# K7410tFFG900Aux.net
KiCad netlist of a schematic drawn in Altium Designer
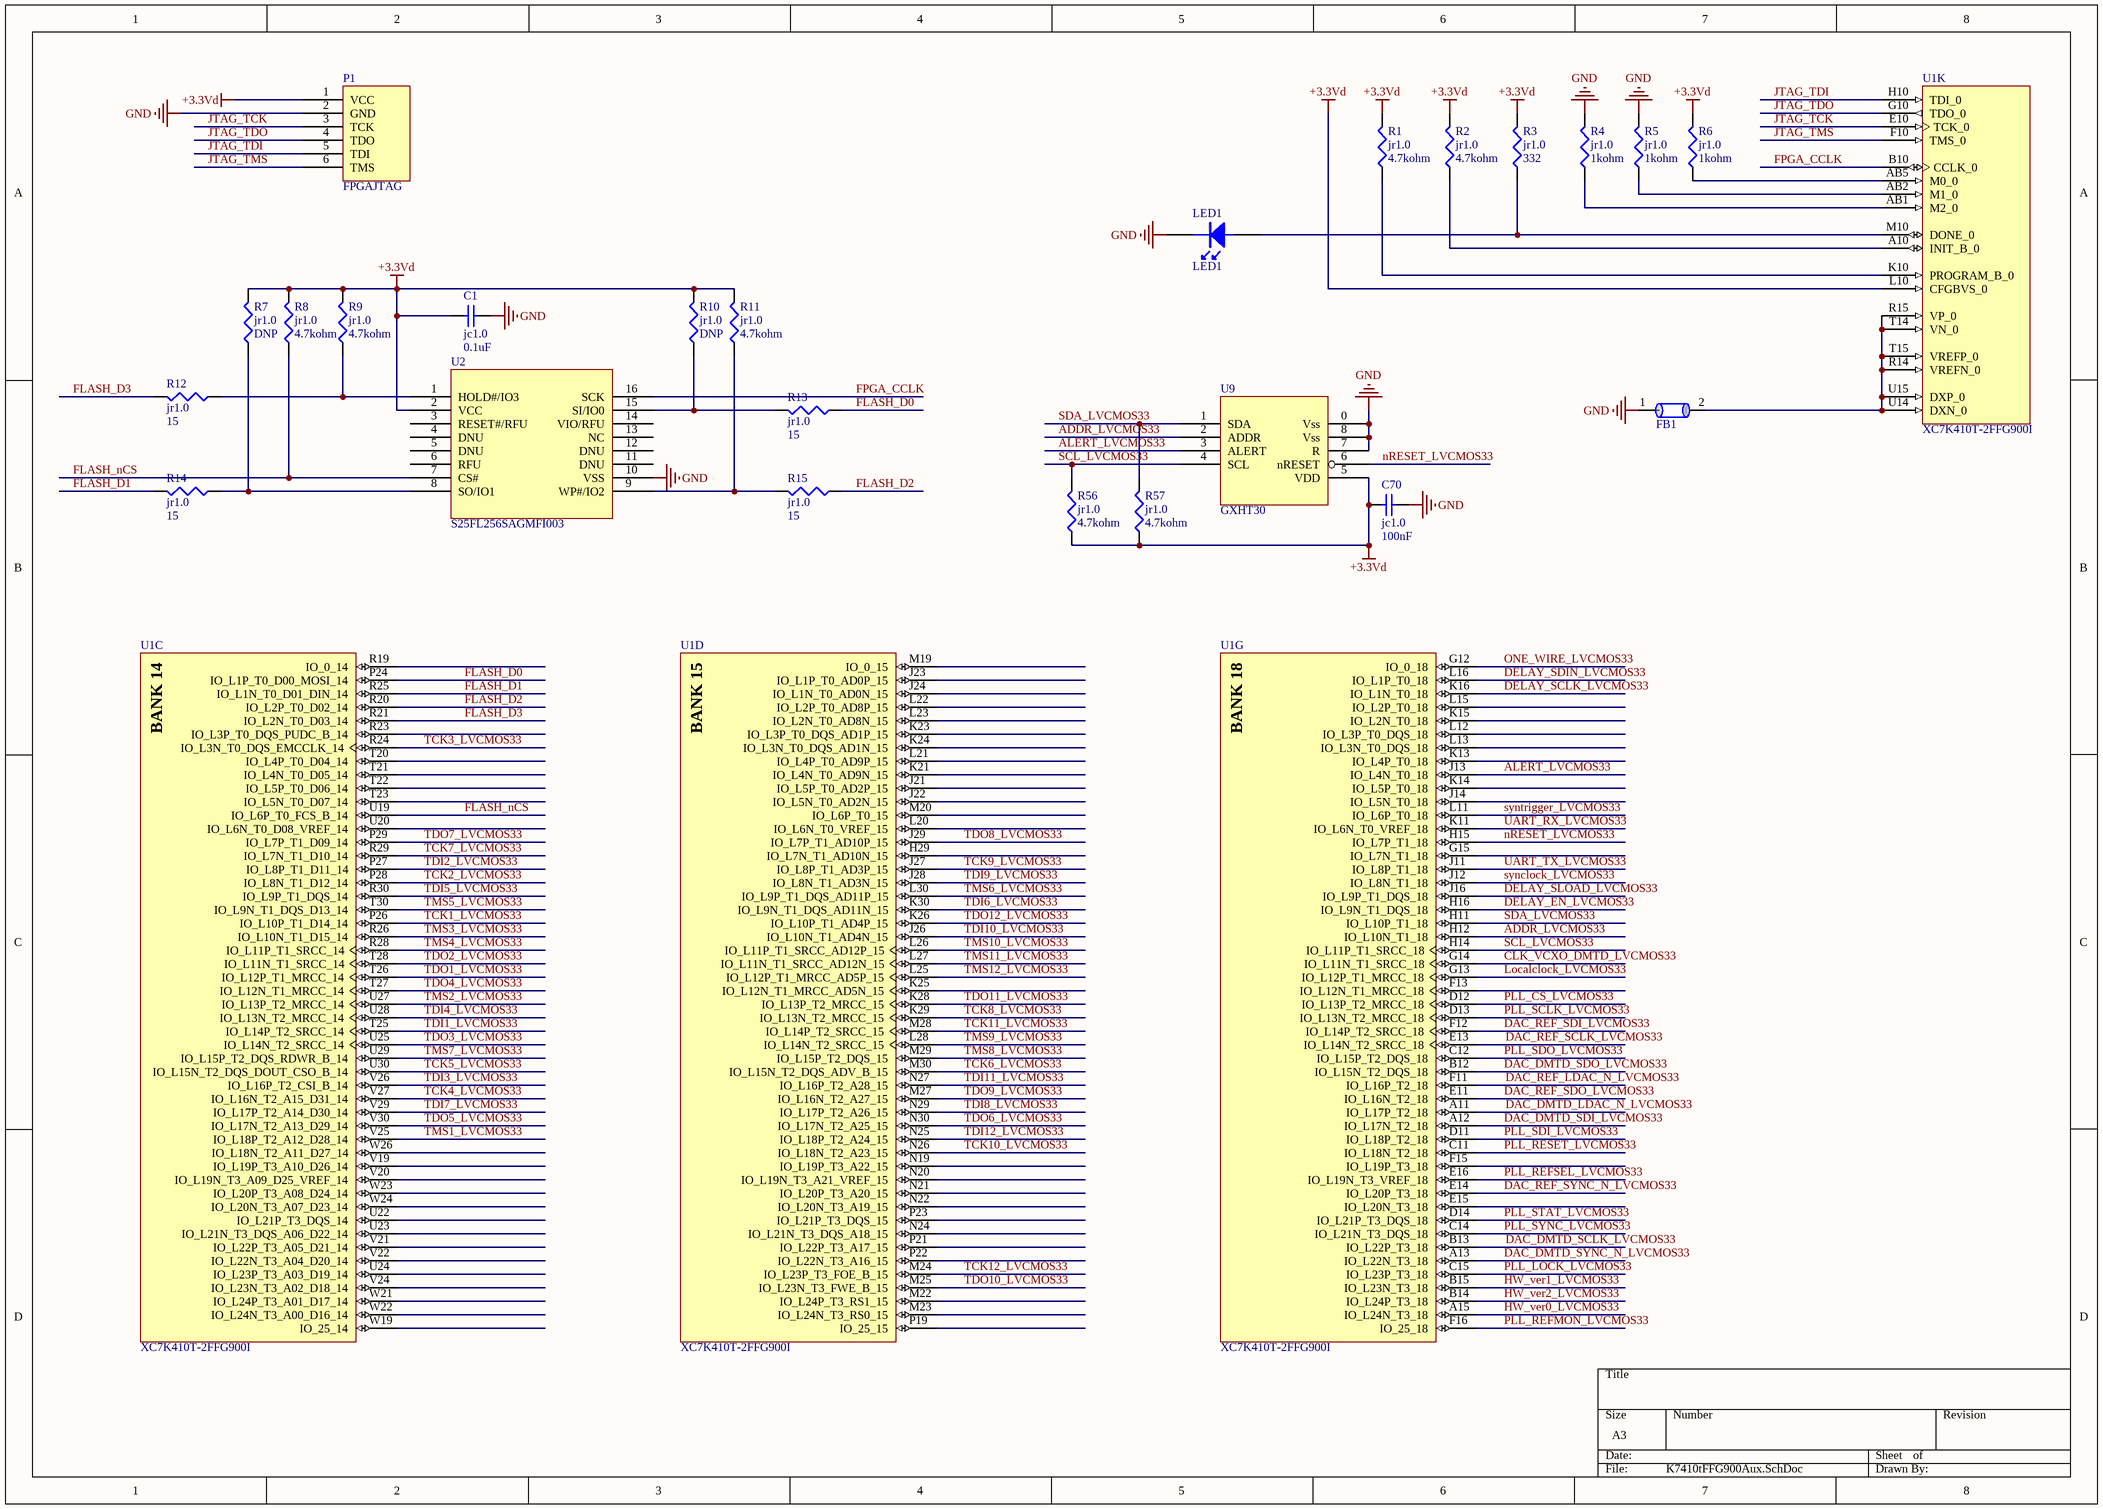
[diagram p0: K7410tFFG900Aux.SchDoc]

(export (version "E")
  (design (tool "Eeschema 10.0.6"))
  (components
    (comp (ref "C1")
      (value "jc1.0")
      (footprint "0402")
      (description "Capacitor")
      (fields (field (name "ALTIUM_VALUE") "0.1uF") (field (name "PUBLISHER") "Altium Limited"))
      (libsource (lib "LIB01DXP2006SchLib") (part "Cap"))
    )
    (comp (ref "C70")
      (value "jc1.0")
      (footprint "0402")
      (description "Capacitor")
      (fields (field (name "ALTIUM_VALUE") "100nF") (field (name "PUBLISHER") "Altium Limited"))
      (libsource (lib "LIB01DXP2006SchLib") (part "Cap"))
    )
    (comp (ref "FB1")
      (value "Ferrite Bead")
      (footprint "0603")
      (libsource (lib "LIB01DXP2006SchLib") (part "FerriteBead"))
    )
    (comp (ref "LED1") (value "LED1") (footprint "LED1") (libsource (lib "LIB01DXP2006SchLib") (part "LED1")))
    (comp (ref "P1")
      (value "FPGAJTAG")
      (footprint "SIP6")
      (libsource (lib "LIB01DXP2006SchLib") (part "FPGAJTAGHEADER"))
    )
    (comp (ref "R1")
      (value "jr1.0")
      (footprint "0402")
      (description "Resistor")
      (fields (field (name "ALTIUM_VALUE") "4.7kohm") (field (name "PUBLISHER") "Altium Limited"))
      (libsource (lib "LIB01DXP2006SchLib") (part "Res"))
    )
    (comp (ref "R2")
      (value "jr1.0")
      (footprint "0402")
      (description "Resistor")
      (fields (field (name "ALTIUM_VALUE") "4.7kohm") (field (name "PUBLISHER") "Altium Limited"))
      (libsource (lib "LIB01DXP2006SchLib") (part "Res"))
    )
    (comp (ref "R3")
      (value "jr1.0")
      (footprint "0402")
      (description "Resistor")
      (fields (field (name "ALTIUM_VALUE") "332") (field (name "PUBLISHER") "Altium Limited"))
      (libsource (lib "LIB01DXP2006SchLib") (part "Res"))
    )
    (comp (ref "R4")
      (value "jr1.0")
      (footprint "0402")
      (description "Resistor")
      (fields (field (name "ALTIUM_VALUE") "1kohm") (field (name "PUBLISHER") "Altium Limited"))
      (libsource (lib "LIB01DXP2006SchLib") (part "Res"))
    )
    (comp (ref "R5")
      (value "jr1.0")
      (footprint "0402")
      (description "Resistor")
      (fields (field (name "ALTIUM_VALUE") "1kohm") (field (name "PUBLISHER") "Altium Limited"))
      (libsource (lib "LIB01DXP2006SchLib") (part "Res"))
    )
    (comp (ref "R6")
      (value "jr1.0")
      (footprint "0402")
      (description "Resistor")
      (fields (field (name "ALTIUM_VALUE") "1kohm") (field (name "PUBLISHER") "Altium Limited"))
      (libsource (lib "LIB01DXP2006SchLib") (part "Res"))
    )
    (comp (ref "R7")
      (value "jr1.0")
      (footprint "0402")
      (description "Resistor")
      (fields (field (name "ALTIUM_VALUE") "DNP") (field (name "PUBLISHER") "Altium Limited"))
      (libsource (lib "LIB01DXP2006SchLib") (part "Res"))
    )
    (comp (ref "R8")
      (value "jr1.0")
      (footprint "0402")
      (description "Resistor")
      (fields (field (name "ALTIUM_VALUE") "4.7kohm") (field (name "PUBLISHER") "Altium Limited"))
      (libsource (lib "LIB01DXP2006SchLib") (part "Res"))
    )
    (comp (ref "R9")
      (value "jr1.0")
      (footprint "0402")
      (description "Resistor")
      (fields (field (name "ALTIUM_VALUE") "4.7kohm") (field (name "PUBLISHER") "Altium Limited"))
      (libsource (lib "LIB01DXP2006SchLib") (part "Res"))
    )
    (comp (ref "R10")
      (value "jr1.0")
      (footprint "0402")
      (description "Resistor")
      (fields (field (name "ALTIUM_VALUE") "DNP") (field (name "PUBLISHER") "Altium Limited"))
      (libsource (lib "LIB01DXP2006SchLib") (part "Res"))
    )
    (comp (ref "R11")
      (value "jr1.0")
      (footprint "0402")
      (description "Resistor")
      (fields (field (name "ALTIUM_VALUE") "4.7kohm") (field (name "PUBLISHER") "Altium Limited"))
      (libsource (lib "LIB01DXP2006SchLib") (part "Res"))
    )
    (comp (ref "R12")
      (value "jr1.0")
      (footprint "0402")
      (description "Resistor")
      (fields (field (name "ALTIUM_VALUE") "15") (field (name "PUBLISHER") "Altium Limited"))
      (libsource (lib "LIB01DXP2006SchLib") (part "Res"))
    )
    (comp (ref "R13")
      (value "jr1.0")
      (footprint "0402")
      (description "Resistor")
      (fields (field (name "ALTIUM_VALUE") "15") (field (name "PUBLISHER") "Altium Limited"))
      (libsource (lib "LIB01DXP2006SchLib") (part "Res"))
    )
    (comp (ref "R14")
      (value "jr1.0")
      (footprint "0402")
      (description "Resistor")
      (fields (field (name "ALTIUM_VALUE") "15") (field (name "PUBLISHER") "Altium Limited"))
      (libsource (lib "LIB01DXP2006SchLib") (part "Res"))
    )
    (comp (ref "R15")
      (value "jr1.0")
      (footprint "0402")
      (description "Resistor")
      (fields (field (name "ALTIUM_VALUE") "15") (field (name "PUBLISHER") "Altium Limited"))
      (libsource (lib "LIB01DXP2006SchLib") (part "Res"))
    )
    (comp (ref "R56")
      (value "jr1.0")
      (footprint "0402")
      (description "Resistor")
      (fields (field (name "ALTIUM_VALUE") "4.7kohm") (field (name "PUBLISHER") "Altium Limited"))
      (libsource (lib "LIB01DXP2006SchLib") (part "Res"))
    )
    (comp (ref "R57")
      (value "jr1.0")
      (footprint "0402")
      (description "Resistor")
      (fields (field (name "ALTIUM_VALUE") "4.7kohm") (field (name "PUBLISHER") "Altium Limited"))
      (libsource (lib "LIB01DXP2006SchLib") (part "Res"))
    )
    (comp (ref "U1")
      (value "XC7K410T-2FFG900I")
      (footprint "FFG900")
      (description "Kintex-7 FPGA, 500 User I/Os, 16 GTX, 900-Ball BGA, Speed Grade 2, Industrial Grade, Pb-Free")
      (fields (field (name "GENERIC PART NUMBER") "XC7K410T") (field (name "MANUFACTURER") "Xilinx"))
      (libsource (lib "Xilinx Kintex-7") (part "XC7K410T-2FFG900I"))
    )
    (comp (ref "U2")
      (value "S25FL256SAGMFI003")
      (footprint "SO3016")
      (libsource (lib "LIB01DXP2006SchLib") (part "S25FL256SAGMFI003"))
    )
    (comp (ref "U9")
      (value "GXHT30")
      (footprint "GXHT30")
      (libsource (lib "LIB01DXP2006SchLib") (part "GXHT30"))
    )
  )
  (nets
    (net (code "1") (name "+3.3Vd") (class "Default")
      (node (ref "C1") (pin "2") (pinfunction "2_2") (pintype "passive"))
      (node (ref "C70") (pin "1") (pinfunction "1_1") (pintype "passive"))
      (node (ref "P1") (pin "1") (pinfunction "VCC_1") (pintype "passive"))
      (node (ref "R1") (pin "2") (pinfunction "2_2") (pintype "passive"))
      (node (ref "R10") (pin "2") (pinfunction "2_2") (pintype "passive"))
      (node (ref "R11") (pin "2") (pinfunction "2_2") (pintype "passive"))
      (node (ref "R2") (pin "2") (pinfunction "2_2") (pintype "passive"))
      (node (ref "R3") (pin "2") (pinfunction "2_2") (pintype "passive"))
      (node (ref "R56") (pin "1") (pinfunction "1_1") (pintype "passive"))
      (node (ref "R57") (pin "1") (pinfunction "1_1") (pintype "passive"))
      (node (ref "R6") (pin "2") (pinfunction "2_2") (pintype "passive"))
      (node (ref "R7") (pin "2") (pinfunction "2_2") (pintype "passive"))
      (node (ref "R8") (pin "2") (pinfunction "2_2") (pintype "passive"))
      (node (ref "R9") (pin "2") (pinfunction "2_2") (pintype "passive"))
      (node (ref "U1") (pin "L10") (pinfunction "CFGBVS_0_L10") (pintype "input"))
      (node (ref "U2") (pin "2") (pinfunction "VCC_2") (pintype "passive"))
      (node (ref "U9") (pin "5") (pinfunction "VDD_5") (pintype "passive"))
    )
    (net (code "2") (name "/ADDR_LVCMOS33") (class "Default")
      (node (ref "U1") (pin "H12") (pinfunction "IO_L10N_T1_18_H12") (pintype "bidirectional"))
      (node (ref "U9") (pin "2") (pinfunction "ADDR_2") (pintype "passive"))
    )
    (net (code "3") (name "/ALERT_LVCMOS33") (class "Default")
      (node (ref "U1") (pin "J13") (pinfunction "IO_L4N_T0_18_J13") (pintype "bidirectional"))
      (node (ref "U9") (pin "3") (pinfunction "ALERT_3") (pintype "passive"))
    )
    (net (code "4") (name "/CLK_VCXO_DMTD_LVCMOS33") (class "Default")
      (node (ref "U1") (pin "G14") (pinfunction "IO_L11N_T1_SRCC_18_G14") (pintype "bidirectional"))
    )
    (net (code "5") (name "/DAC_DMTD_LDAC_N_LVCMOS33") (class "Default")
      (node (ref "U1") (pin "A11") (pinfunction "IO_L17P_T2_18_A11") (pintype "bidirectional"))
    )
    (net (code "6") (name "/DAC_DMTD_SCLK_LVCMOS33") (class "Default")
      (node (ref "U1") (pin "B13") (pinfunction "IO_L22P_T3_18_B13") (pintype "bidirectional"))
    )
    (net (code "7") (name "/DAC_DMTD_SDI_LVCMOS33") (class "Default")
      (node (ref "U1") (pin "A12") (pinfunction "IO_L17N_T2_18_A12") (pintype "bidirectional"))
    )
    (net (code "8") (name "/DAC_DMTD_SDO_LVCMOS33") (class "Default")
      (node (ref "U1") (pin "B12") (pinfunction "IO_L15N_T2_DQS_18_B12") (pintype "bidirectional"))
    )
    (net (code "9") (name "/DAC_DMTD_SYNC_N_LVCMOS33") (class "Default")
      (node (ref "U1") (pin "A13") (pinfunction "IO_L22N_T3_18_A13") (pintype "bidirectional"))
    )
    (net (code "10") (name "/DAC_REF_LDAC_N_LVCMOS33") (class "Default")
      (node (ref "U1") (pin "F11") (pinfunction "IO_L16P_T2_18_F11") (pintype "bidirectional"))
    )
    (net (code "11") (name "/DAC_REF_SCLK_LVCMOS33") (class "Default")
      (node (ref "U1") (pin "E13") (pinfunction "IO_L14N_T2_SRCC_18_E13") (pintype "bidirectional"))
    )
    (net (code "12") (name "/DAC_REF_SDI_LVCMOS33") (class "Default")
      (node (ref "U1") (pin "F12") (pinfunction "IO_L14P_T2_SRCC_18_F12") (pintype "bidirectional"))
    )
    (net (code "13") (name "/DAC_REF_SDO_LVCMOS33") (class "Default")
      (node (ref "U1") (pin "E11") (pinfunction "IO_L16N_T2_18_E11") (pintype "bidirectional"))
    )
    (net (code "14") (name "/DAC_REF_SYNC_N_LVCMOS33") (class "Default")
      (node (ref "U1") (pin "E14") (pinfunction "IO_L20P_T3_18_E14") (pintype "bidirectional"))
    )
    (net (code "15") (name "/DELAY_EN_LVCMOS33") (class "Default")
      (node (ref "U1") (pin "H16") (pinfunction "IO_L9N_T1_DQS_18_H16") (pintype "bidirectional"))
    )
    (net (code "16") (name "/DELAY_SCLK_LVCMOS33") (class "Default")
      (node (ref "U1") (pin "K16") (pinfunction "IO_L1N_T0_18_K16") (pintype "bidirectional"))
    )
    (net (code "17") (name "/DELAY_SDIN_LVCMOS33") (class "Default")
      (node (ref "U1") (pin "L16") (pinfunction "IO_L1P_T0_18_L16") (pintype "bidirectional"))
    )
    (net (code "18") (name "/DELAY_SLOAD_LVCMOS33") (class "Default")
      (node (ref "U1") (pin "J16") (pinfunction "IO_L9P_T1_DQS_18_J16") (pintype "bidirectional"))
    )
    (net (code "19") (name "/FLASH_D0") (class "Default")
      (node (ref "R13") (pin "1") (pinfunction "1_1") (pintype "passive"))
      (node (ref "U1") (pin "P24") (pinfunction "IO_L1P_T0_D00_MOSI_14_P24") (pintype "bidirectional"))
    )
    (net (code "20") (name "/FLASH_D1") (class "Default")
      (node (ref "R14") (pin "2") (pinfunction "2_2") (pintype "passive"))
      (node (ref "U1") (pin "R25") (pinfunction "IO_L1N_T0_D01_DIN_14_R25") (pintype "bidirectional"))
    )
    (net (code "21") (name "/FLASH_D2") (class "Default")
      (node (ref "R15") (pin "1") (pinfunction "1_1") (pintype "passive"))
      (node (ref "U1") (pin "R20") (pinfunction "IO_L2P_T0_D02_14_R20") (pintype "bidirectional"))
    )
    (net (code "22") (name "/FLASH_D3") (class "Default")
      (node (ref "R12") (pin "2") (pinfunction "2_2") (pintype "passive"))
      (node (ref "U1") (pin "R21") (pinfunction "IO_L2N_T0_D03_14_R21") (pintype "bidirectional"))
    )
    (net (code "23") (name "/FLASH_nCS") (class "Default")
      (node (ref "R8") (pin "1") (pinfunction "1_1") (pintype "passive"))
      (node (ref "U1") (pin "U19") (pinfunction "IO_L6P_T0_FCS_B_14_U19") (pintype "bidirectional"))
      (node (ref "U2") (pin "7") (pinfunction "CS#_7") (pintype "passive"))
    )
    (net (code "24") (name "/FPGA_CCLK") (class "Default")
      (node (ref "U1") (pin "B10") (pinfunction "CCLK_0_B10") (pintype "bidirectional"))
      (node (ref "U2") (pin "16") (pinfunction "SCK_16") (pintype "passive"))
    )
    (net (code "25") (name "/HW_ver0_LVCMOS33") (class "Default")
      (node (ref "U1") (pin "A15") (pinfunction "IO_L24N_T3_18_A15") (pintype "bidirectional"))
    )
    (net (code "26") (name "/HW_ver1_LVCMOS33") (class "Default")
      (node (ref "U1") (pin "B15") (pinfunction "IO_L23N_T3_18_B15") (pintype "bidirectional"))
    )
    (net (code "27") (name "/HW_ver2_LVCMOS33") (class "Default")
      (node (ref "U1") (pin "B14") (pinfunction "IO_L24P_T3_18_B14") (pintype "bidirectional"))
    )
    (net (code "28") (name "/JTAG_TCK") (class "Default")
      (node (ref "P1") (pin "3") (pinfunction "TCK_3") (pintype "passive"))
      (node (ref "U1") (pin "E10") (pinfunction "TCK_0_E10") (pintype "input"))
    )
    (net (code "29") (name "/JTAG_TDI") (class "Default")
      (node (ref "P1") (pin "5") (pinfunction "TDI_5") (pintype "passive"))
      (node (ref "U1") (pin "H10") (pinfunction "TDI_0_H10") (pintype "input"))
    )
    (net (code "30") (name "/JTAG_TDO") (class "Default")
      (node (ref "P1") (pin "4") (pinfunction "TDO_4") (pintype "passive"))
      (node (ref "U1") (pin "G10") (pinfunction "TDO_0_G10") (pintype "output"))
    )
    (net (code "31") (name "/JTAG_TMS") (class "Default")
      (node (ref "P1") (pin "6") (pinfunction "TMS_6") (pintype "passive"))
      (node (ref "U1") (pin "F10") (pinfunction "TMS_0_F10") (pintype "input"))
    )
    (net (code "32") (name "/Localclock_LVCMOS33") (class "Default")
      (node (ref "U1") (pin "G13") (pinfunction "IO_L12P_T1_MRCC_18_G13") (pintype "bidirectional"))
    )
    (net (code "33") (name "/ONE_WIRE_LVCMOS33") (class "Default")
      (node (ref "U1") (pin "G12") (pinfunction "IO_0_18_G12") (pintype "bidirectional"))
    )
    (net (code "34") (name "/PLL_CS_LVCMOS33") (class "Default")
      (node (ref "U1") (pin "D12") (pinfunction "IO_L13P_T2_MRCC_18_D12") (pintype "bidirectional"))
    )
    (net (code "35") (name "/PLL_LOCK_LVCMOS33") (class "Default")
      (node (ref "U1") (pin "C15") (pinfunction "IO_L23P_T3_18_C15") (pintype "bidirectional"))
    )
    (net (code "36") (name "/PLL_REFMON_LVCMOS33") (class "Default")
      (node (ref "U1") (pin "F16") (pinfunction "IO_25_18_F16") (pintype "bidirectional"))
    )
    (net (code "37") (name "/PLL_REFSEL_LVCMOS33") (class "Default")
      (node (ref "U1") (pin "E16") (pinfunction "IO_L19N_T3_VREF_18_E16") (pintype "bidirectional"))
    )
    (net (code "38") (name "/PLL_RESET_LVCMOS33") (class "Default")
      (node (ref "U1") (pin "C11") (pinfunction "IO_L18N_T2_18_C11") (pintype "bidirectional"))
    )
    (net (code "39") (name "/PLL_SCLK_LVCMOS33") (class "Default")
      (node (ref "U1") (pin "D13") (pinfunction "IO_L13N_T2_MRCC_18_D13") (pintype "bidirectional"))
    )
    (net (code "40") (name "/PLL_SDI_LVCMOS33") (class "Default")
      (node (ref "U1") (pin "D11") (pinfunction "IO_L18P_T2_18_D11") (pintype "bidirectional"))
    )
    (net (code "41") (name "/PLL_SDO_LVCMOS33") (class "Default")
      (node (ref "U1") (pin "C12") (pinfunction "IO_L15P_T2_DQS_18_C12") (pintype "bidirectional"))
    )
    (net (code "42") (name "/PLL_STAT_LVCMOS33") (class "Default")
      (node (ref "U1") (pin "D14") (pinfunction "IO_L21P_T3_DQS_18_D14") (pintype "bidirectional"))
    )
    (net (code "43") (name "/PLL_SYNC_LVCMOS33") (class "Default")
      (node (ref "U1") (pin "C14") (pinfunction "IO_L21N_T3_DQS_18_C14") (pintype "bidirectional"))
    )
    (net (code "44") (name "/SCL_LVCMOS33") (class "Default")
      (node (ref "R56") (pin "2") (pinfunction "2_2") (pintype "passive"))
      (node (ref "U1") (pin "H14") (pinfunction "IO_L11P_T1_SRCC_18_H14") (pintype "bidirectional"))
      (node (ref "U9") (pin "4") (pinfunction "SCL_4") (pintype "passive"))
    )
    (net (code "45") (name "/SDA_LVCMOS33") (class "Default")
      (node (ref "R57") (pin "2") (pinfunction "2_2") (pintype "passive"))
      (node (ref "U1") (pin "H11") (pinfunction "IO_L10P_T1_18_H11") (pintype "bidirectional"))
      (node (ref "U9") (pin "1") (pinfunction "SDA_1") (pintype "passive"))
    )
    (net (code "46") (name "/TCK1_LVCMOS33") (class "Default")
      (node (ref "U1") (pin "P26") (pinfunction "IO_L10P_T1_D14_14_P26") (pintype "bidirectional"))
    )
    (net (code "47") (name "/TCK2_LVCMOS33") (class "Default")
      (node (ref "U1") (pin "P28") (pinfunction "IO_L8N_T1_D12_14_P28") (pintype "bidirectional"))
    )
    (net (code "48") (name "/TCK3_LVCMOS33") (class "Default")
      (node (ref "U1") (pin "R24") (pinfunction "IO_L3N_T0_DQS_EMCCLK_14_R24") (pintype "bidirectional"))
    )
    (net (code "49") (name "/TCK4_LVCMOS33") (class "Default")
      (node (ref "U1") (pin "V27") (pinfunction "IO_L16N_T2_A15_D31_14_V27") (pintype "bidirectional"))
    )
    (net (code "50") (name "/TCK5_LVCMOS33") (class "Default")
      (node (ref "U1") (pin "U30") (pinfunction "IO_L15N_T2_DQS_DOUT_CSO_B_14_U30") (pintype "bidirectional"))
    )
    (net (code "51") (name "/TCK6_LVCMOS33") (class "Default")
      (node (ref "U1") (pin "M30") (pinfunction "IO_L15N_T2_DQS_ADV_B_15_M30") (pintype "bidirectional"))
    )
    (net (code "52") (name "/TCK7_LVCMOS33") (class "Default")
      (node (ref "U1") (pin "R29") (pinfunction "IO_L7N_T1_D10_14_R29") (pintype "bidirectional"))
    )
    (net (code "53") (name "/TCK8_LVCMOS33") (class "Default")
      (node (ref "U1") (pin "K29") (pinfunction "IO_L13N_T2_MRCC_15_K29") (pintype "bidirectional"))
    )
    (net (code "54") (name "/TCK9_LVCMOS33") (class "Default")
      (node (ref "U1") (pin "J27") (pinfunction "IO_L8P_T1_AD3P_15_J27") (pintype "bidirectional"))
    )
    (net (code "55") (name "/TCK10_LVCMOS33") (class "Default")
      (node (ref "U1") (pin "N26") (pinfunction "IO_L18N_T2_A23_15_N26") (pintype "bidirectional"))
    )
    (net (code "56") (name "/TCK11_LVCMOS33") (class "Default")
      (node (ref "U1") (pin "M28") (pinfunction "IO_L14P_T2_SRCC_15_M28") (pintype "bidirectional"))
    )
    (net (code "57") (name "/TCK12_LVCMOS33") (class "Default")
      (node (ref "U1") (pin "M24") (pinfunction "IO_L23P_T3_FOE_B_15_M24") (pintype "bidirectional"))
    )
    (net (code "58") (name "/TDI1_LVCMOS33") (class "Default")
      (node (ref "U1") (pin "T25") (pinfunction "IO_L14P_T2_SRCC_14_T25") (pintype "bidirectional"))
    )
    (net (code "59") (name "/TDI2_LVCMOS33") (class "Default")
      (node (ref "U1") (pin "P27") (pinfunction "IO_L8P_T1_D11_14_P27") (pintype "bidirectional"))
    )
    (net (code "60") (name "/TDI3_LVCMOS33") (class "Default")
      (node (ref "U1") (pin "V26") (pinfunction "IO_L16P_T2_CSI_B_14_V26") (pintype "bidirectional"))
    )
    (net (code "61") (name "/TDI4_LVCMOS33") (class "Default")
      (node (ref "U1") (pin "U28") (pinfunction "IO_L13N_T2_MRCC_14_U28") (pintype "bidirectional"))
    )
    (net (code "62") (name "/TDI5_LVCMOS33") (class "Default")
      (node (ref "U1") (pin "R30") (pinfunction "IO_L9P_T1_DQS_14_R30") (pintype "bidirectional"))
    )
    (net (code "63") (name "/TDI6_LVCMOS33") (class "Default")
      (node (ref "U1") (pin "K30") (pinfunction "IO_L9N_T1_DQS_AD11N_15_K30") (pintype "bidirectional"))
    )
    (net (code "64") (name "/TDI7_LVCMOS33") (class "Default")
      (node (ref "U1") (pin "V29") (pinfunction "IO_L17P_T2_A14_D30_14_V29") (pintype "bidirectional"))
    )
    (net (code "65") (name "/TDI8_LVCMOS33") (class "Default")
      (node (ref "U1") (pin "N29") (pinfunction "IO_L17P_T2_A26_15_N29") (pintype "bidirectional"))
    )
    (net (code "66") (name "/TDI9_LVCMOS33") (class "Default")
      (node (ref "U1") (pin "J28") (pinfunction "IO_L8N_T1_AD3N_15_J28") (pintype "bidirectional"))
    )
    (net (code "67") (name "/TDI10_LVCMOS33") (class "Default")
      (node (ref "U1") (pin "J26") (pinfunction "IO_L10N_T1_AD4N_15_J26") (pintype "bidirectional"))
    )
    (net (code "68") (name "/TDI11_LVCMOS33") (class "Default")
      (node (ref "U1") (pin "N27") (pinfunction "IO_L16P_T2_A28_15_N27") (pintype "bidirectional"))
    )
    (net (code "69") (name "/TDI12_LVCMOS33") (class "Default")
      (node (ref "U1") (pin "N25") (pinfunction "IO_L18P_T2_A24_15_N25") (pintype "bidirectional"))
    )
    (net (code "70") (name "/TDO1_LVCMOS33") (class "Default")
      (node (ref "U1") (pin "T26") (pinfunction "IO_L12P_T1_MRCC_14_T26") (pintype "bidirectional"))
    )
    (net (code "71") (name "/TDO2_LVCMOS33") (class "Default")
      (node (ref "U1") (pin "T28") (pinfunction "IO_L11N_T1_SRCC_14_T28") (pintype "bidirectional"))
    )
    (net (code "72") (name "/TDO3_LVCMOS33") (class "Default")
      (node (ref "U1") (pin "U25") (pinfunction "IO_L14N_T2_SRCC_14_U25") (pintype "bidirectional"))
    )
    (net (code "73") (name "/TDO4_LVCMOS33") (class "Default")
      (node (ref "U1") (pin "T27") (pinfunction "IO_L12N_T1_MRCC_14_T27") (pintype "bidirectional"))
    )
    (net (code "74") (name "/TDO5_LVCMOS33") (class "Default")
      (node (ref "U1") (pin "V30") (pinfunction "IO_L17N_T2_A13_D29_14_V30") (pintype "bidirectional"))
    )
    (net (code "75") (name "/TDO6_LVCMOS33") (class "Default")
      (node (ref "U1") (pin "N30") (pinfunction "IO_L17N_T2_A25_15_N30") (pintype "bidirectional"))
    )
    (net (code "76") (name "/TDO7_LVCMOS33") (class "Default")
      (node (ref "U1") (pin "P29") (pinfunction "IO_L7P_T1_D09_14_P29") (pintype "bidirectional"))
    )
    (net (code "77") (name "/TDO8_LVCMOS33") (class "Default")
      (node (ref "U1") (pin "J29") (pinfunction "IO_L7P_T1_AD10P_15_J29") (pintype "bidirectional"))
    )
    (net (code "78") (name "/TDO9_LVCMOS33") (class "Default")
      (node (ref "U1") (pin "M27") (pinfunction "IO_L16N_T2_A27_15_M27") (pintype "bidirectional"))
    )
    (net (code "79") (name "/TDO10_LVCMOS33") (class "Default")
      (node (ref "U1") (pin "M25") (pinfunction "IO_L23N_T3_FWE_B_15_M25") (pintype "bidirectional"))
    )
    (net (code "80") (name "/TDO11_LVCMOS33") (class "Default")
      (node (ref "U1") (pin "K28") (pinfunction "IO_L13P_T2_MRCC_15_K28") (pintype "bidirectional"))
    )
    (net (code "81") (name "/TDO12_LVCMOS33") (class "Default")
      (node (ref "U1") (pin "K26") (pinfunction "IO_L10P_T1_AD4P_15_K26") (pintype "bidirectional"))
    )
    (net (code "82") (name "/TMS1_LVCMOS33") (class "Default")
      (node (ref "U1") (pin "V25") (pinfunction "IO_L18P_T2_A12_D28_14_V25") (pintype "bidirectional"))
    )
    (net (code "83") (name "/TMS2_LVCMOS33") (class "Default")
      (node (ref "U1") (pin "U27") (pinfunction "IO_L13P_T2_MRCC_14_U27") (pintype "bidirectional"))
    )
    (net (code "84") (name "/TMS3_LVCMOS33") (class "Default")
      (node (ref "U1") (pin "R26") (pinfunction "IO_L10N_T1_D15_14_R26") (pintype "bidirectional"))
    )
    (net (code "85") (name "/TMS4_LVCMOS33") (class "Default")
      (node (ref "U1") (pin "R28") (pinfunction "IO_L11P_T1_SRCC_14_R28") (pintype "bidirectional"))
    )
    (net (code "86") (name "/TMS5_LVCMOS33") (class "Default")
      (node (ref "U1") (pin "T30") (pinfunction "IO_L9N_T1_DQS_D13_14_T30") (pintype "bidirectional"))
    )
    (net (code "87") (name "/TMS6_LVCMOS33") (class "Default")
      (node (ref "U1") (pin "L30") (pinfunction "IO_L9P_T1_DQS_AD11P_15_L30") (pintype "bidirectional"))
    )
    (net (code "88") (name "/TMS7_LVCMOS33") (class "Default")
      (node (ref "U1") (pin "U29") (pinfunction "IO_L15P_T2_DQS_RDWR_B_14_U29") (pintype "bidirectional"))
    )
    (net (code "89") (name "/TMS8_LVCMOS33") (class "Default")
      (node (ref "U1") (pin "M29") (pinfunction "IO_L15P_T2_DQS_15_M29") (pintype "bidirectional"))
    )
    (net (code "90") (name "/TMS9_LVCMOS33") (class "Default")
      (node (ref "U1") (pin "L28") (pinfunction "IO_L14N_T2_SRCC_15_L28") (pintype "bidirectional"))
    )
    (net (code "91") (name "/TMS10_LVCMOS33") (class "Default")
      (node (ref "U1") (pin "L26") (pinfunction "IO_L11P_T1_SRCC_AD12P_15_L26") (pintype "bidirectional"))
    )
    (net (code "92") (name "/TMS11_LVCMOS33") (class "Default")
      (node (ref "U1") (pin "L27") (pinfunction "IO_L11N_T1_SRCC_AD12N_15_L27") (pintype "bidirectional"))
    )
    (net (code "93") (name "/TMS12_LVCMOS33") (class "Default")
      (node (ref "U1") (pin "L25") (pinfunction "IO_L12P_T1_MRCC_AD5P_15_L25") (pintype "bidirectional"))
    )
    (net (code "94") (name "/UART_RX_LVCMOS33") (class "Default")
      (node (ref "U1") (pin "K11") (pinfunction "IO_L6N_T0_VREF_18_K11") (pintype "bidirectional"))
    )
    (net (code "95") (name "/UART_TX_LVCMOS33") (class "Default")
      (node (ref "U1") (pin "J11") (pinfunction "IO_L8P_T1_18_J11") (pintype "bidirectional"))
    )
    (net (code "96") (name "/nRESET_LVCMOS33") (class "Default")
      (node (ref "U1") (pin "H15") (pinfunction "IO_L7P_T1_18_H15") (pintype "bidirectional"))
      (node (ref "U9") (pin "6") (pinfunction "nRESET_6") (pintype "passive"))
    )
    (net (code "97") (name "/synclock_LVCMOS33") (class "Default")
      (node (ref "U1") (pin "J12") (pinfunction "IO_L8N_T1_18_J12") (pintype "bidirectional"))
    )
    (net (code "98") (name "/syntrigger_LVCMOS33") (class "Default")
      (node (ref "U1") (pin "L11") (pinfunction "IO_L6P_T0_18_L11") (pintype "bidirectional"))
    )
    (net (code "99") (name "GND") (class "Default")
      (node (ref "C1") (pin "1") (pinfunction "1_1") (pintype "passive"))
      (node (ref "C70") (pin "2") (pinfunction "2_2") (pintype "passive"))
      (node (ref "FB1") (pin "1") (pinfunction "X_1") (pintype "passive"))
      (node (ref "LED1") (pin "2") (pinfunction "2_2") (pintype "passive"))
      (node (ref "P1") (pin "2") (pinfunction "GND_2") (pintype "passive"))
      (node (ref "R4") (pin "2") (pinfunction "2_2") (pintype "passive"))
      (node (ref "R5") (pin "2") (pinfunction "2_2") (pintype "passive"))
      (node (ref "U2") (pin "10") (pinfunction "VSS_10") (pintype "passive"))
      (node (ref "U9") (pin "0") (pinfunction "Vss_0") (pintype "passive"))
      (node (ref "U9") (pin "7") (pinfunction "R_7") (pintype "passive"))
      (node (ref "U9") (pin "8") (pinfunction "Vss_8") (pintype "passive"))
    )
    (net (code "100") (name "Net-(FB1-Y)") (class "Default")
      (node (ref "FB1") (pin "2") (pinfunction "Y_2") (pintype "passive"))
      (node (ref "U1") (pin "R14") (pinfunction "VREFN_0_R14") (pintype "input"))
      (node (ref "U1") (pin "R15") (pinfunction "VP_0_R15") (pintype "input"))
      (node (ref "U1") (pin "T14") (pinfunction "VN_0_T14") (pintype "input"))
      (node (ref "U1") (pin "T15") (pinfunction "VREFP_0_T15") (pintype "input"))
      (node (ref "U1") (pin "U14") (pinfunction "DXN_0_U14") (pintype "input"))
      (node (ref "U1") (pin "U15") (pinfunction "DXP_0_U15") (pintype "input"))
    )
    (net (code "101") (name "Net-(U1K-DONE_0)") (class "Default")
      (node (ref "LED1") (pin "1") (pinfunction "1_1") (pintype "passive"))
      (node (ref "R3") (pin "1") (pinfunction "1_1") (pintype "passive"))
      (node (ref "U1") (pin "M10") (pinfunction "DONE_0_M10") (pintype "bidirectional"))
    )
    (net (code "102") (name "Net-(U1K-INIT_B_0)") (class "Default")
      (node (ref "R2") (pin "1") (pinfunction "1_1") (pintype "passive"))
      (node (ref "U1") (pin "A10") (pinfunction "INIT_B_0_A10") (pintype "bidirectional"))
    )
    (net (code "103") (name "Net-(U1K-M0_0)") (class "Default")
      (node (ref "R6") (pin "1") (pinfunction "1_1") (pintype "passive"))
      (node (ref "U1") (pin "AB5") (pinfunction "M0_0_AB5") (pintype "input"))
    )
    (net (code "104") (name "Net-(U1K-M1_0)") (class "Default")
      (node (ref "R5") (pin "1") (pinfunction "1_1") (pintype "passive"))
      (node (ref "U1") (pin "AB2") (pinfunction "M1_0_AB2") (pintype "input"))
    )
    (net (code "105") (name "Net-(U1K-M2_0)") (class "Default")
      (node (ref "R4") (pin "1") (pinfunction "1_1") (pintype "passive"))
      (node (ref "U1") (pin "AB1") (pinfunction "M2_0_AB1") (pintype "input"))
    )
    (net (code "106") (name "Net-(U1K-PROGRAM_B_0)") (class "Default")
      (node (ref "R1") (pin "1") (pinfunction "1_1") (pintype "passive"))
      (node (ref "U1") (pin "K10") (pinfunction "PROGRAM_B_0_K10") (pintype "input"))
    )
    (net (code "107") (name "Net-(U2-HOLD#{slash}IO3)") (class "Default")
      (node (ref "R12") (pin "1") (pinfunction "1_1") (pintype "passive"))
      (node (ref "R9") (pin "1") (pinfunction "1_1") (pintype "passive"))
      (node (ref "U2") (pin "1") (pinfunction "HOLD#/IO3_1") (pintype "passive"))
    )
    (net (code "108") (name "Net-(U2-SI{slash}IO0)") (class "Default")
      (node (ref "R10") (pin "1") (pinfunction "1_1") (pintype "passive"))
      (node (ref "R13") (pin "2") (pinfunction "2_2") (pintype "passive"))
      (node (ref "U2") (pin "15") (pinfunction "SI/IO0_15") (pintype "passive"))
    )
    (net (code "109") (name "Net-(U2-SO{slash}IO1)") (class "Default")
      (node (ref "R14") (pin "1") (pinfunction "1_1") (pintype "passive"))
      (node (ref "R7") (pin "1") (pinfunction "1_1") (pintype "passive"))
      (node (ref "U2") (pin "8") (pinfunction "SO/IO1_8") (pintype "passive"))
    )
    (net (code "110") (name "Net-(U2-WP#{slash}IO2)") (class "Default")
      (node (ref "R11") (pin "1") (pinfunction "1_1") (pintype "passive"))
      (node (ref "R15") (pin "2") (pinfunction "2_2") (pintype "passive"))
      (node (ref "U2") (pin "9") (pinfunction "WP#/IO2_9") (pintype "passive"))
    )
    (net (code "111") (name "unconnected-(U1C-IO_0_14-PadR19)") (class "Default")
      (node (ref "U1") (pin "R19") (pinfunction "IO_0_14_R19") (pintype "bidirectional"))
    )
    (net (code "112") (name "unconnected-(U1C-IO_25_14-PadW19)") (class "Default")
      (node (ref "U1") (pin "W19") (pinfunction "IO_25_14_W19") (pintype "bidirectional"))
    )
    (net (code "113") (name "unconnected-(U1C-IO_L3P_T0_DQS_PUDC_B_14-PadR23)") (class "Default")
      (node (ref "U1") (pin "R23") (pinfunction "IO_L3P_T0_DQS_PUDC_B_14_R23") (pintype "bidirectional"))
    )
    (net (code "114") (name "unconnected-(U1C-IO_L4N_T0_D05_14-PadT21)") (class "Default")
      (node (ref "U1") (pin "T21") (pinfunction "IO_L4N_T0_D05_14_T21") (pintype "bidirectional"))
    )
    (net (code "115") (name "unconnected-(U1C-IO_L4P_T0_D04_14-PadT20)") (class "Default")
      (node (ref "U1") (pin "T20") (pinfunction "IO_L4P_T0_D04_14_T20") (pintype "bidirectional"))
    )
    (net (code "116") (name "unconnected-(U1C-IO_L5N_T0_D07_14-PadT23)") (class "Default")
      (node (ref "U1") (pin "T23") (pinfunction "IO_L5N_T0_D07_14_T23") (pintype "bidirectional"))
    )
    (net (code "117") (name "unconnected-(U1C-IO_L5P_T0_D06_14-PadT22)") (class "Default")
      (node (ref "U1") (pin "T22") (pinfunction "IO_L5P_T0_D06_14_T22") (pintype "bidirectional"))
    )
    (net (code "118") (name "unconnected-(U1C-IO_L6N_T0_D08_VREF_14-PadU20)") (class "Default")
      (node (ref "U1") (pin "U20") (pinfunction "IO_L6N_T0_D08_VREF_14_U20") (pintype "bidirectional"))
    )
    (net (code "119") (name "unconnected-(U1C-IO_L18N_T2_A11_D27_14-PadW26)") (class "Default")
      (node (ref "U1") (pin "W26") (pinfunction "IO_L18N_T2_A11_D27_14_W26") (pintype "bidirectional"))
    )
    (net (code "120") (name "unconnected-(U1C-IO_L19N_T3_A09_D25_VREF_14-PadV20)") (class "Default")
      (node (ref "U1") (pin "V20") (pinfunction "IO_L19N_T3_A09_D25_VREF_14_V20") (pintype "bidirectional"))
    )
    (net (code "121") (name "unconnected-(U1C-IO_L19P_T3_A10_D26_14-PadV19)") (class "Default")
      (node (ref "U1") (pin "V19") (pinfunction "IO_L19P_T3_A10_D26_14_V19") (pintype "bidirectional"))
    )
    (net (code "122") (name "unconnected-(U1C-IO_L20N_T3_A07_D23_14-PadW24)") (class "Default")
      (node (ref "U1") (pin "W24") (pinfunction "IO_L20N_T3_A07_D23_14_W24") (pintype "bidirectional"))
    )
    (net (code "123") (name "unconnected-(U1C-IO_L20P_T3_A08_D24_14-PadW23)") (class "Default")
      (node (ref "U1") (pin "W23") (pinfunction "IO_L20P_T3_A08_D24_14_W23") (pintype "bidirectional"))
    )
    (net (code "124") (name "unconnected-(U1C-IO_L21N_T3_DQS_A06_D22_14-PadU23)") (class "Default")
      (node (ref "U1") (pin "U23") (pinfunction "IO_L21N_T3_DQS_A06_D22_14_U23") (pintype "bidirectional"))
    )
    (net (code "125") (name "unconnected-(U1C-IO_L21P_T3_DQS_14-PadU22)") (class "Default")
      (node (ref "U1") (pin "U22") (pinfunction "IO_L21P_T3_DQS_14_U22") (pintype "bidirectional"))
    )
    (net (code "126") (name "unconnected-(U1C-IO_L22N_T3_A04_D20_14-PadV22)") (class "Default")
      (node (ref "U1") (pin "V22") (pinfunction "IO_L22N_T3_A04_D20_14_V22") (pintype "bidirectional"))
    )
    (net (code "127") (name "unconnected-(U1C-IO_L22P_T3_A05_D21_14-PadV21)") (class "Default")
      (node (ref "U1") (pin "V21") (pinfunction "IO_L22P_T3_A05_D21_14_V21") (pintype "bidirectional"))
    )
    (net (code "128") (name "unconnected-(U1C-IO_L23N_T3_A02_D18_14-PadV24)") (class "Default")
      (node (ref "U1") (pin "V24") (pinfunction "IO_L23N_T3_A02_D18_14_V24") (pintype "bidirectional"))
    )
    (net (code "129") (name "unconnected-(U1C-IO_L23P_T3_A03_D19_14-PadU24)") (class "Default")
      (node (ref "U1") (pin "U24") (pinfunction "IO_L23P_T3_A03_D19_14_U24") (pintype "bidirectional"))
    )
    (net (code "130") (name "unconnected-(U1C-IO_L24N_T3_A00_D16_14-PadW22)") (class "Default")
      (node (ref "U1") (pin "W22") (pinfunction "IO_L24N_T3_A00_D16_14_W22") (pintype "bidirectional"))
    )
    (net (code "131") (name "unconnected-(U1C-IO_L24P_T3_A01_D17_14-PadW21)") (class "Default")
      (node (ref "U1") (pin "W21") (pinfunction "IO_L24P_T3_A01_D17_14_W21") (pintype "bidirectional"))
    )
    (net (code "132") (name "unconnected-(U1D-IO_0_15-PadM19)") (class "Default")
      (node (ref "U1") (pin "M19") (pinfunction "IO_0_15_M19") (pintype "bidirectional"))
    )
    (net (code "133") (name "unconnected-(U1D-IO_25_15-PadP19)") (class "Default")
      (node (ref "U1") (pin "P19") (pinfunction "IO_25_15_P19") (pintype "bidirectional"))
    )
    (net (code "134") (name "unconnected-(U1D-IO_L1N_T0_AD0N_15-PadJ24)") (class "Default")
      (node (ref "U1") (pin "J24") (pinfunction "IO_L1N_T0_AD0N_15_J24") (pintype "bidirectional"))
    )
    (net (code "135") (name "unconnected-(U1D-IO_L1P_T0_AD0P_15-PadJ23)") (class "Default")
      (node (ref "U1") (pin "J23") (pinfunction "IO_L1P_T0_AD0P_15_J23") (pintype "bidirectional"))
    )
    (net (code "136") (name "unconnected-(U1D-IO_L2N_T0_AD8N_15-PadL23)") (class "Default")
      (node (ref "U1") (pin "L23") (pinfunction "IO_L2N_T0_AD8N_15_L23") (pintype "bidirectional"))
    )
    (net (code "137") (name "unconnected-(U1D-IO_L2P_T0_AD8P_15-PadL22)") (class "Default")
      (node (ref "U1") (pin "L22") (pinfunction "IO_L2P_T0_AD8P_15_L22") (pintype "bidirectional"))
    )
    (net (code "138") (name "unconnected-(U1D-IO_L3N_T0_DQS_AD1N_15-PadK24)") (class "Default")
      (node (ref "U1") (pin "K24") (pinfunction "IO_L3N_T0_DQS_AD1N_15_K24") (pintype "bidirectional"))
    )
    (net (code "139") (name "unconnected-(U1D-IO_L3P_T0_DQS_AD1P_15-PadK23)") (class "Default")
      (node (ref "U1") (pin "K23") (pinfunction "IO_L3P_T0_DQS_AD1P_15_K23") (pintype "bidirectional"))
    )
    (net (code "140") (name "unconnected-(U1D-IO_L4N_T0_AD9N_15-PadK21)") (class "Default")
      (node (ref "U1") (pin "K21") (pinfunction "IO_L4N_T0_AD9N_15_K21") (pintype "bidirectional"))
    )
    (net (code "141") (name "unconnected-(U1D-IO_L4P_T0_AD9P_15-PadL21)") (class "Default")
      (node (ref "U1") (pin "L21") (pinfunction "IO_L4P_T0_AD9P_15_L21") (pintype "bidirectional"))
    )
    (net (code "142") (name "unconnected-(U1D-IO_L5N_T0_AD2N_15-PadJ22)") (class "Default")
      (node (ref "U1") (pin "J22") (pinfunction "IO_L5N_T0_AD2N_15_J22") (pintype "bidirectional"))
    )
    (net (code "143") (name "unconnected-(U1D-IO_L5P_T0_AD2P_15-PadJ21)") (class "Default")
      (node (ref "U1") (pin "J21") (pinfunction "IO_L5P_T0_AD2P_15_J21") (pintype "bidirectional"))
    )
    (net (code "144") (name "unconnected-(U1D-IO_L6N_T0_VREF_15-PadL20)") (class "Default")
      (node (ref "U1") (pin "L20") (pinfunction "IO_L6N_T0_VREF_15_L20") (pintype "bidirectional"))
    )
    (net (code "145") (name "unconnected-(U1D-IO_L6P_T0_15-PadM20)") (class "Default")
      (node (ref "U1") (pin "M20") (pinfunction "IO_L6P_T0_15_M20") (pintype "bidirectional"))
    )
    (net (code "146") (name "unconnected-(U1D-IO_L7N_T1_AD10N_15-PadH29)") (class "Default")
      (node (ref "U1") (pin "H29") (pinfunction "IO_L7N_T1_AD10N_15_H29") (pintype "bidirectional"))
    )
    (net (code "147") (name "unconnected-(U1D-IO_L12N_T1_MRCC_AD5N_15-PadK25)") (class "Default")
      (node (ref "U1") (pin "K25") (pinfunction "IO_L12N_T1_MRCC_AD5N_15_K25") (pintype "bidirectional"))
    )
    (net (code "148") (name "unconnected-(U1D-IO_L19N_T3_A21_VREF_15-PadN20)") (class "Default")
      (node (ref "U1") (pin "N20") (pinfunction "IO_L19N_T3_A21_VREF_15_N20") (pintype "bidirectional"))
    )
    (net (code "149") (name "unconnected-(U1D-IO_L19P_T3_A22_15-PadN19)") (class "Default")
      (node (ref "U1") (pin "N19") (pinfunction "IO_L19P_T3_A22_15_N19") (pintype "bidirectional"))
    )
    (net (code "150") (name "unconnected-(U1D-IO_L20N_T3_A19_15-PadN22)") (class "Default")
      (node (ref "U1") (pin "N22") (pinfunction "IO_L20N_T3_A19_15_N22") (pintype "bidirectional"))
    )
    (net (code "151") (name "unconnected-(U1D-IO_L20P_T3_A20_15-PadN21)") (class "Default")
      (node (ref "U1") (pin "N21") (pinfunction "IO_L20P_T3_A20_15_N21") (pintype "bidirectional"))
    )
    (net (code "152") (name "unconnected-(U1D-IO_L21N_T3_DQS_A18_15-PadN24)") (class "Default")
      (node (ref "U1") (pin "N24") (pinfunction "IO_L21N_T3_DQS_A18_15_N24") (pintype "bidirectional"))
    )
    (net (code "153") (name "unconnected-(U1D-IO_L21P_T3_DQS_15-PadP23)") (class "Default")
      (node (ref "U1") (pin "P23") (pinfunction "IO_L21P_T3_DQS_15_P23") (pintype "bidirectional"))
    )
    (net (code "154") (name "unconnected-(U1D-IO_L22N_T3_A16_15-PadP22)") (class "Default")
      (node (ref "U1") (pin "P22") (pinfunction "IO_L22N_T3_A16_15_P22") (pintype "bidirectional"))
    )
    (net (code "155") (name "unconnected-(U1D-IO_L22P_T3_A17_15-PadP21)") (class "Default")
      (node (ref "U1") (pin "P21") (pinfunction "IO_L22P_T3_A17_15_P21") (pintype "bidirectional"))
    )
    (net (code "156") (name "unconnected-(U1D-IO_L24N_T3_RS0_15-PadM23)") (class "Default")
      (node (ref "U1") (pin "M23") (pinfunction "IO_L24N_T3_RS0_15_M23") (pintype "bidirectional"))
    )
    (net (code "157") (name "unconnected-(U1D-IO_L24P_T3_RS1_15-PadM22)") (class "Default")
      (node (ref "U1") (pin "M22") (pinfunction "IO_L24P_T3_RS1_15_M22") (pintype "bidirectional"))
    )
    (net (code "158") (name "unconnected-(U1G-IO_L2N_T0_18-PadK15)") (class "Default")
      (node (ref "U1") (pin "K15") (pinfunction "IO_L2N_T0_18_K15") (pintype "bidirectional"))
    )
    (net (code "159") (name "unconnected-(U1G-IO_L2P_T0_18-PadL15)") (class "Default")
      (node (ref "U1") (pin "L15") (pinfunction "IO_L2P_T0_18_L15") (pintype "bidirectional"))
    )
    (net (code "160") (name "unconnected-(U1G-IO_L3N_T0_DQS_18-PadL13)") (class "Default")
      (node (ref "U1") (pin "L13") (pinfunction "IO_L3N_T0_DQS_18_L13") (pintype "bidirectional"))
    )
    (net (code "161") (name "unconnected-(U1G-IO_L3P_T0_DQS_18-PadL12)") (class "Default")
      (node (ref "U1") (pin "L12") (pinfunction "IO_L3P_T0_DQS_18_L12") (pintype "bidirectional"))
    )
    (net (code "162") (name "unconnected-(U1G-IO_L4P_T0_18-PadK13)") (class "Default")
      (node (ref "U1") (pin "K13") (pinfunction "IO_L4P_T0_18_K13") (pintype "bidirectional"))
    )
    (net (code "163") (name "unconnected-(U1G-IO_L5N_T0_18-PadJ14)") (class "Default")
      (node (ref "U1") (pin "J14") (pinfunction "IO_L5N_T0_18_J14") (pintype "bidirectional"))
    )
    (net (code "164") (name "unconnected-(U1G-IO_L5P_T0_18-PadK14)") (class "Default")
      (node (ref "U1") (pin "K14") (pinfunction "IO_L5P_T0_18_K14") (pintype "bidirectional"))
    )
    (net (code "165") (name "unconnected-(U1G-IO_L7N_T1_18-PadG15)") (class "Default")
      (node (ref "U1") (pin "G15") (pinfunction "IO_L7N_T1_18_G15") (pintype "bidirectional"))
    )
    (net (code "166") (name "unconnected-(U1G-IO_L12N_T1_MRCC_18-PadF13)") (class "Default")
      (node (ref "U1") (pin "F13") (pinfunction "IO_L12N_T1_MRCC_18_F13") (pintype "bidirectional"))
    )
    (net (code "167") (name "unconnected-(U1G-IO_L19P_T3_18-PadF15)") (class "Default")
      (node (ref "U1") (pin "F15") (pinfunction "IO_L19P_T3_18_F15") (pintype "bidirectional"))
    )
    (net (code "168") (name "unconnected-(U1G-IO_L20N_T3_18-PadE15)") (class "Default")
      (node (ref "U1") (pin "E15") (pinfunction "IO_L20N_T3_18_E15") (pintype "bidirectional"))
    )
    (net (code "169") (name "unconnected-(U2-DNU-Pad4)") (class "Default")
      (node (ref "U2") (pin "4") (pinfunction "DNU_4") (pintype "passive"))
    )
    (net (code "170") (name "unconnected-(U2-DNU-Pad5)") (class "Default")
      (node (ref "U2") (pin "5") (pinfunction "DNU_5") (pintype "passive"))
    )
    (net (code "171") (name "unconnected-(U2-DNU-Pad11)") (class "Default")
      (node (ref "U2") (pin "11") (pinfunction "DNU_11") (pintype "passive"))
    )
    (net (code "172") (name "unconnected-(U2-DNU-Pad12)") (class "Default")
      (node (ref "U2") (pin "12") (pinfunction "DNU_12") (pintype "passive"))
    )
    (net (code "173") (name "unconnected-(U2-NC-Pad13)") (class "Default")
      (node (ref "U2") (pin "13") (pinfunction "NC_13") (pintype "passive"))
    )
    (net (code "174") (name "unconnected-(U2-RESET#{slash}RFU-Pad3)") (class "Default")
      (node (ref "U2") (pin "3") (pinfunction "RESET#/RFU_3") (pintype "passive"))
    )
    (net (code "175") (name "unconnected-(U2-RFU-Pad6)") (class "Default")
      (node (ref "U2") (pin "6") (pinfunction "RFU_6") (pintype "passive"))
    )
    (net (code "176") (name "unconnected-(U2-VIO{slash}RFU-Pad14)") (class "Default")
      (node (ref "U2") (pin "14") (pinfunction "VIO/RFU_14") (pintype "passive"))
    )
  )
)
